# design_block_rev3_4.net
KiCad netlist of a schematic drawn in EAGLE
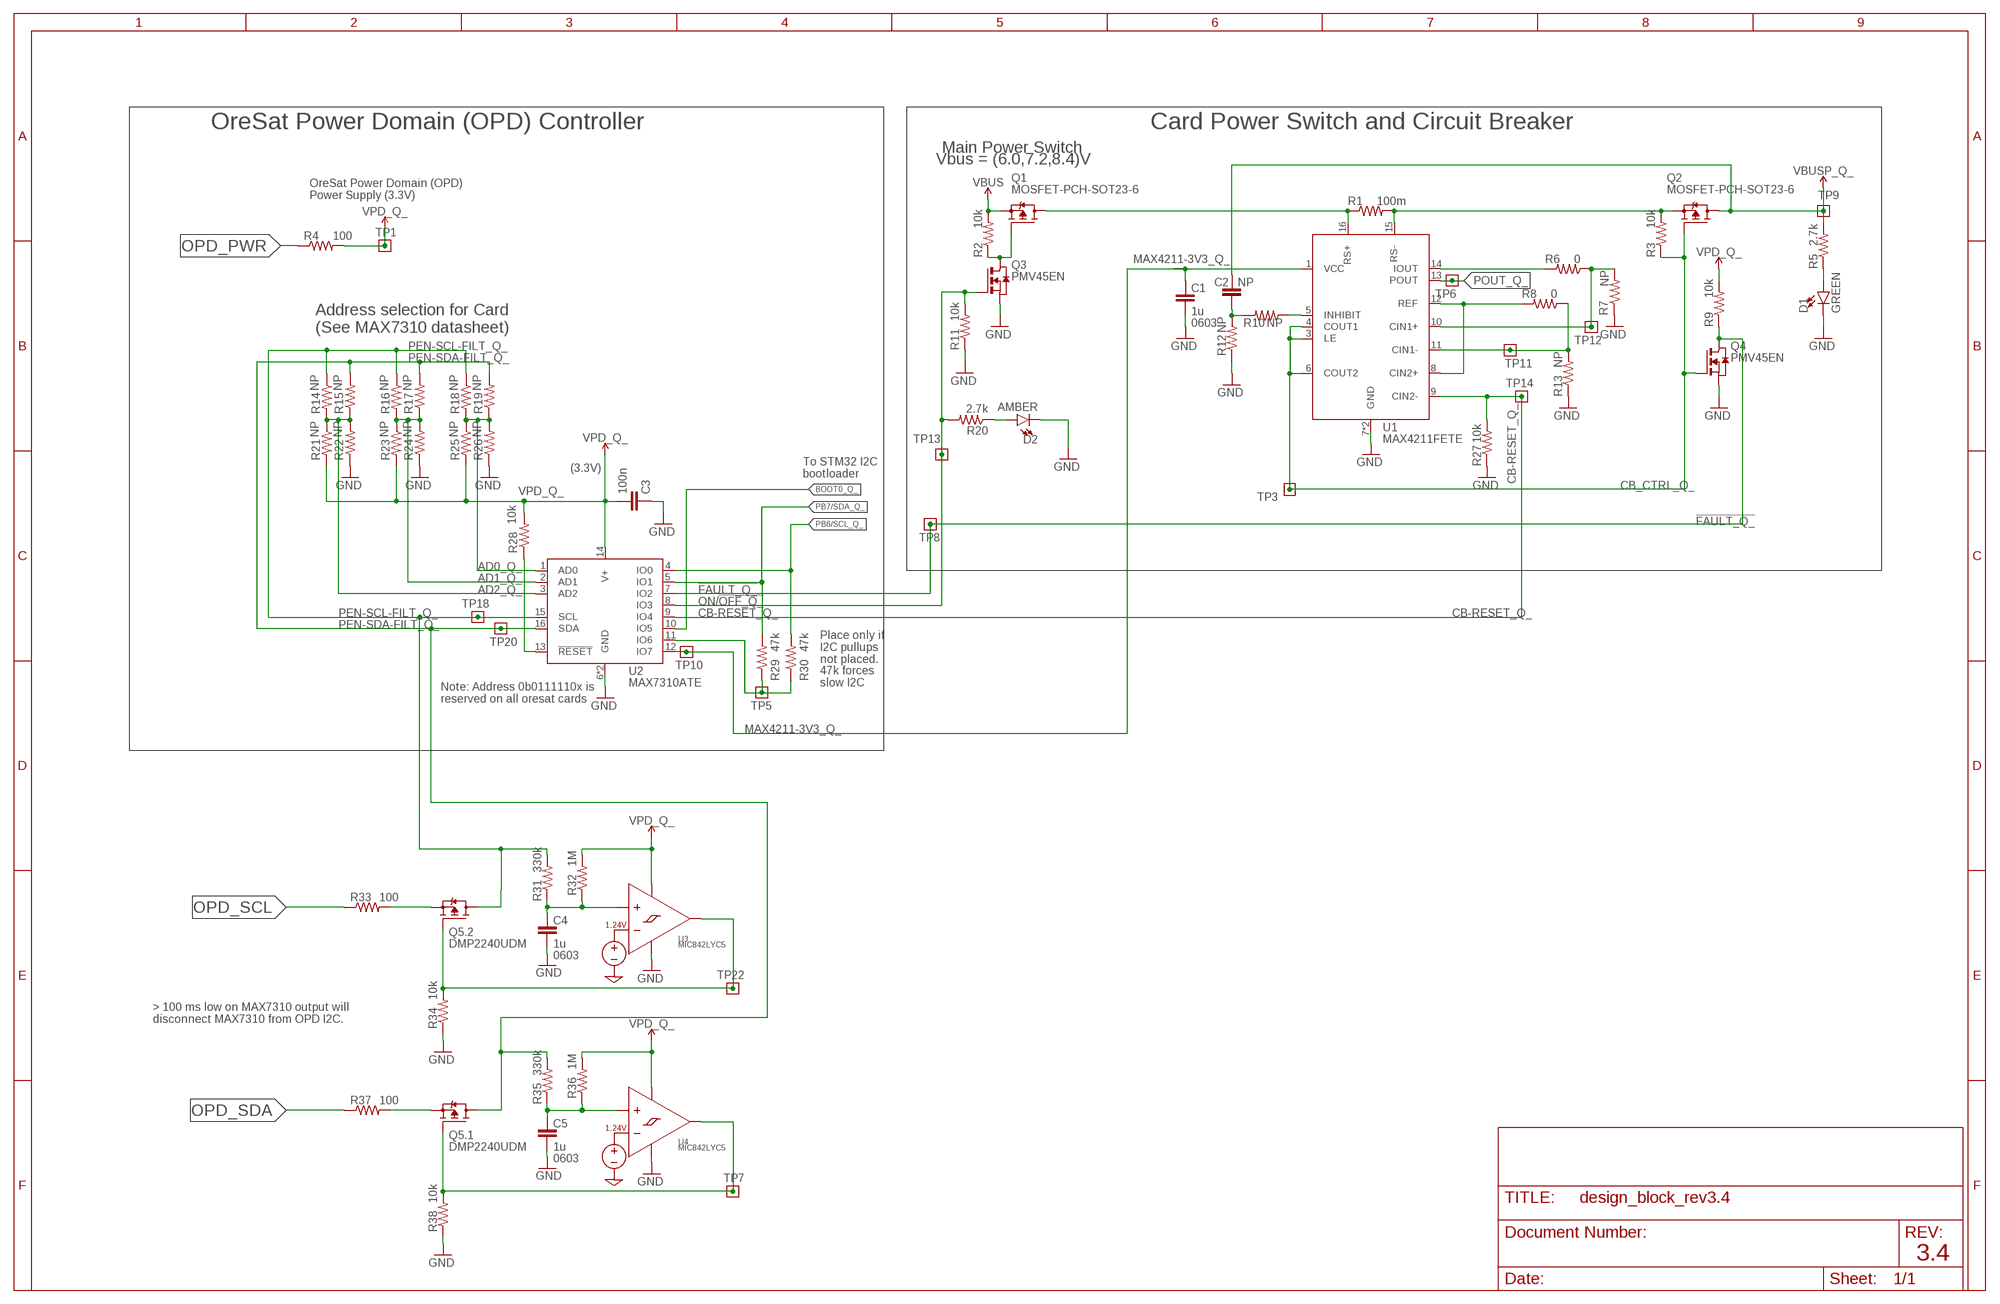
[diagram p0: schematic, sheet 1]

(export (version "E")
  (design (tool "Eeschema 10.0.6"))
  (components
    (comp (ref "C1")
      (value "1u")
      (footprint "eagle-import:.0603-B-NOSILK")
      (fields (field (name "MFR") "Yageo") (field (name "MPN") "CC0603KRX7R7BB105"))
      (libsource (lib "eagle-import") (part "C-EU0603-B-NOSILK"))
    )
    (comp (ref "C2")
      (value "NP")
      (footprint "eagle-import:.0402-B-NOSILK")
      (libsource (lib "eagle-import") (part "rcl_custom_C-EU0402-B-NOSILK"))
    )
    (comp (ref "C3")
      (value "100n")
      (footprint "eagle-import:.0402-B-NOSILK")
      (fields (field (name "MFR") "Samsung") (field (name "MPN") "CL05B104KO5NNNC"))
      (libsource (lib "eagle-import") (part "rcl_custom_C-EU0402-B-NOSILK"))
    )
    (comp (ref "C4")
      (value "1u")
      (footprint "eagle-import:.0603-B-NOSILK")
      (fields (field (name "MFR") "Yageo") (field (name "MPN") "CC0603KRX7R7BB105"))
      (libsource (lib "eagle-import") (part "C-EU0603-B-NOSILK"))
    )
    (comp (ref "C5")
      (value "1u")
      (footprint "eagle-import:.0603-B-NOSILK")
      (fields (field (name "MFR") "Yageo") (field (name "MPN") "CC0603KRX7R7BB105"))
      (libsource (lib "eagle-import") (part "C-EU0603-B-NOSILK"))
    )
    (comp (ref "D1")
      (value "GREEN")
      (footprint "eagle-import:LED-0603")
      (fields (field (name "MFR") "Rohm") (field (name "MPN") "SML-E12M8WT86"))
      (libsource (lib "eagle-import") (part "LED-GREEN0603"))
    )
    (comp (ref "D2")
      (value "AMBER")
      (footprint "eagle-import:LED-0603")
      (fields (field (name "MFR") "Inolux") (field (name "MPN") "IN-S63AT5A"))
      (libsource (lib "eagle-import") (part "LED-GREEN0603"))
    )
    (comp (ref "Q1")
      (value "MOSFET-PCH-SOT23-6")
      (footprint "eagle-import:SOT23-6")
      (fields (field (name "MFR") "Diodes Inc") (field (name "MPN") "DMP3050LVT-7"))
      (libsource (lib "eagle-import") (part "MOSFET-PCH-SOT23-6"))
    )
    (comp (ref "Q2")
      (value "MOSFET-PCH-SOT23-6")
      (footprint "eagle-import:SOT23-6")
      (fields (field (name "MFR") "Diodes Inc") (field (name "MPN") "DMP3050LVT-7"))
      (libsource (lib "eagle-import") (part "MOSFET-PCH-SOT23-6"))
    )
    (comp (ref "Q3")
      (value "PMV45EN")
      (footprint "eagle-import:SOT23")
      (fields (field (name "MFR") "Nexperia") (field (name "MPN") "PMV45EN2R"))
      (libsource (lib "eagle-import") (part "PMV45EN"))
    )
    (comp (ref "Q4")
      (value "PMV45EN")
      (footprint "eagle-import:SOT23")
      (fields (field (name "MFR") "Nexperia") (field (name "MPN") "PMV45EN2R"))
      (libsource (lib "eagle-import") (part "PMV45EN"))
    )
    (comp (ref "Q5")
      (value "DMP2240UDM")
      (footprint "eagle-import:SOT23-6")
      (fields
        (field (name "DIS") "Digi-Key")
        (field (name "DPN") "DMP2240UDMDICT-ND")
        (field (name "MFR") "Diodes Inc")
        (field (name "MPN") "DMP2240UDM")
      )
      (libsource (lib "eagle-import") (part "Q-MOSFET-PCH-dual-SOT23-6_MOSFET-PCH-SOT23-6"))
    )
    (comp (ref "R1")
      (value "100m")
      (footprint "eagle-import:R1206")
      (fields (field (name "MFR") "Stackpole") (field (name "MPN") "CSR1206FTR100"))
      (libsource (lib "eagle-import") (part "R-US_R1206"))
    )
    (comp (ref "R2")
      (value "10k")
      (footprint "eagle-import:.0402-B-NOSILK")
      (fields (field (name "MFR") "Yageo") (field (name "MPN") "RC0402FR-0710KL"))
      (libsource (lib "eagle-import") (part "R-US_0402-B-NOSILK"))
    )
    (comp (ref "R3")
      (value "10k")
      (footprint "eagle-import:.0402-B-NOSILK")
      (fields (field (name "MFR") "Yageo") (field (name "MPN") "RC0402FR-0710KL"))
      (libsource (lib "eagle-import") (part "R-US_0402-B-NOSILK"))
    )
    (comp (ref "R4")
      (value "100")
      (footprint "eagle-import:.0402-B-NOSILK")
      (fields (field (name "MFR") "Yageo") (field (name "MPN") "RC0402FR-07100RL"))
      (libsource (lib "eagle-import") (part "R-US_0402-B-NOSILK"))
    )
    (comp (ref "R5")
      (value "2.7k")
      (footprint "eagle-import:.0402-B-NOSILK")
      (fields (field (name "MFR") "TE Connectivity") (field (name "MPN") "CRGCQ0402F2K7"))
      (libsource (lib "eagle-import") (part "R-US_0402-B-NOSILK"))
    )
    (comp (ref "R6")
      (value "0")
      (footprint "eagle-import:.0402-B-NOSILK")
      (fields (field (name "MFR") "Yageo") (field (name "MPN") "RC0402JR-070RL"))
      (libsource (lib "eagle-import") (part "R-US_0402-B-NOSILK"))
    )
    (comp (ref "R7")
      (value "NP")
      (footprint "eagle-import:.0402-B-NOSILK")
      (fields (field (name "MFR") "Samsung") (field (name "MPN") "RC1005F6653CS"))
      (libsource (lib "eagle-import") (part "R-US_0402-B-NOSILK"))
    )
    (comp (ref "R8")
      (value "0")
      (footprint "eagle-import:.0402-B-NOSILK")
      (fields (field (name "MFR") "Yageo") (field (name "MPN") "RC0402JR-070RL"))
      (libsource (lib "eagle-import") (part "R-US_0402-B-NOSILK"))
    )
    (comp (ref "R9")
      (value "10k")
      (footprint "eagle-import:.0402-B-NOSILK")
      (fields (field (name "MFR") "Yageo") (field (name "MPN") "RC0402FR-0710KL"))
      (libsource (lib "eagle-import") (part "R-US_0402-B-NOSILK"))
    )
    (comp (ref "R10")
      (value "NP")
      (footprint "eagle-import:.0402-B-NOSILK")
      (fields (field (name "MFR") "Samsung") (field (name "MPN") "RC1005F6653CS"))
      (libsource (lib "eagle-import") (part "R-US_0402-B-NOSILK"))
    )
    (comp (ref "R11")
      (value "10k")
      (footprint "eagle-import:.0402-B-NOSILK")
      (fields (field (name "MFR") "Yageo") (field (name "MPN") "RC0402FR-0710KL"))
      (libsource (lib "eagle-import") (part "R-US_0402-B-NOSILK"))
    )
    (comp (ref "R12")
      (value "NP")
      (footprint "eagle-import:.0402-B-NOSILK")
      (fields (field (name "MFR") "Samsung") (field (name "MPN") "RC1005F6653CS"))
      (libsource (lib "eagle-import") (part "R-US_0402-B-NOSILK"))
    )
    (comp (ref "R13")
      (value "NP")
      (footprint "eagle-import:.0402-B-NOSILK")
      (fields (field (name "MFR") "Samsung") (field (name "MPN") "RC1005F6653CS"))
      (libsource (lib "eagle-import") (part "R-US_0402-B-NOSILK"))
    )
    (comp (ref "R14")
      (value "NP")
      (footprint "eagle-import:.0402-B-NOSILK")
      (fields (field (name "MFR") "Samsung") (field (name "MPN") "RC1005F6653CS"))
      (libsource (lib "eagle-import") (part "R-US_0402-B-NOSILK"))
    )
    (comp (ref "R15")
      (value "NP")
      (footprint "eagle-import:.0402-B-NOSILK")
      (fields (field (name "MFR") "Samsung") (field (name "MPN") "RC1005F6653CS"))
      (libsource (lib "eagle-import") (part "R-US_0402-B-NOSILK"))
    )
    (comp (ref "R16")
      (value "NP")
      (footprint "eagle-import:.0402-B-NOSILK")
      (fields (field (name "MFR") "Samsung") (field (name "MPN") "RC1005F6653CS"))
      (libsource (lib "eagle-import") (part "R-US_0402-B-NOSILK"))
    )
    (comp (ref "R17")
      (value "NP")
      (footprint "eagle-import:.0402-B-NOSILK")
      (fields (field (name "MFR") "Samsung") (field (name "MPN") "RC1005F6653CS"))
      (libsource (lib "eagle-import") (part "R-US_0402-B-NOSILK"))
    )
    (comp (ref "R18")
      (value "NP")
      (footprint "eagle-import:.0402-B-NOSILK")
      (fields (field (name "MFR") "Samsung") (field (name "MPN") "RC1005F6653CS"))
      (libsource (lib "eagle-import") (part "R-US_0402-B-NOSILK"))
    )
    (comp (ref "R19")
      (value "NP")
      (footprint "eagle-import:.0402-B-NOSILK")
      (fields (field (name "MFR") "Samsung") (field (name "MPN") "RC1005F6653CS"))
      (libsource (lib "eagle-import") (part "R-US_0402-B-NOSILK"))
    )
    (comp (ref "R20")
      (value "2.7k")
      (footprint "eagle-import:.0402-B-NOSILK")
      (fields (field (name "MFR") "TE Connectivity ") (field (name "MPN") "CRGCQ0402F2K7"))
      (libsource (lib "eagle-import") (part "R-US_0402-B-NOSILK"))
    )
    (comp (ref "R21")
      (value "NP")
      (footprint "eagle-import:.0402-B-NOSILK")
      (fields (field (name "MFR") "Samsung") (field (name "MPN") "RC1005F6653CS"))
      (libsource (lib "eagle-import") (part "R-US_0402-B-NOSILK"))
    )
    (comp (ref "R22")
      (value "NP")
      (footprint "eagle-import:.0402-B-NOSILK")
      (fields (field (name "MFR") "Samsung") (field (name "MPN") "RC1005F6653CS"))
      (libsource (lib "eagle-import") (part "R-US_0402-B-NOSILK"))
    )
    (comp (ref "R23")
      (value "NP")
      (footprint "eagle-import:.0402-B-NOSILK")
      (fields (field (name "MFR") "Samsung") (field (name "MPN") "RC1005F6653CS"))
      (libsource (lib "eagle-import") (part "R-US_0402-B-NOSILK"))
    )
    (comp (ref "R24")
      (value "NP")
      (footprint "eagle-import:.0402-B-NOSILK")
      (fields (field (name "MFR") "Samsung") (field (name "MPN") "RC1005F6653CS"))
      (libsource (lib "eagle-import") (part "R-US_0402-B-NOSILK"))
    )
    (comp (ref "R25")
      (value "NP")
      (footprint "eagle-import:.0402-B-NOSILK")
      (fields (field (name "MFR") "Samsung") (field (name "MPN") "RC1005F6653CS"))
      (libsource (lib "eagle-import") (part "R-US_0402-B-NOSILK"))
    )
    (comp (ref "R26")
      (value "NP")
      (footprint "eagle-import:.0402-B-NOSILK")
      (fields (field (name "MFR") "Samsung") (field (name "MPN") "RC1005F6653CS"))
      (libsource (lib "eagle-import") (part "R-US_0402-B-NOSILK"))
    )
    (comp (ref "R27")
      (value "10k")
      (footprint "eagle-import:.0402-B-NOSILK")
      (fields (field (name "MFR") "Yageo") (field (name "MPN") "RC0402FR-0710KL"))
      (libsource (lib "eagle-import") (part "R-US_0402-B-NOSILK"))
    )
    (comp (ref "R28")
      (value "10k")
      (footprint "eagle-import:.0402-B-NOSILK")
      (fields (field (name "MFR") "Yageo") (field (name "MPN") "RC0402FR-0710KL"))
      (libsource (lib "eagle-import") (part "R-US_0402-B-NOSILK"))
    )
    (comp (ref "R29")
      (value "47k")
      (footprint "eagle-import:.0402-B-NOSILK")
      (fields (field (name "MFR") "Yageo") (field (name "MPN") "RC0402FR-0747KL"))
      (libsource (lib "eagle-import") (part "R-US_0402-B-NOSILK"))
    )
    (comp (ref "R30")
      (value "47k")
      (footprint "eagle-import:.0402-B-NOSILK")
      (fields (field (name "MFR") "Yageo") (field (name "MPN") "RC0402FR-0747KL"))
      (libsource (lib "eagle-import") (part "R-US_0402-B-NOSILK"))
    )
    (comp (ref "R31")
      (value "330k")
      (footprint "eagle-import:.0402-B-NOSILK")
      (fields (field (name "MFR") "Vishay") (field (name "MPN") "MCS04020C3303FE000"))
      (libsource (lib "eagle-import") (part "R-US_0402-B-NOSILK"))
    )
    (comp (ref "R32")
      (value "1M")
      (footprint "eagle-import:.0402-B-NOSILK")
      (fields (field (name "MFR") "Yageo") (field (name "MPN") "RC0402FR-071ML"))
      (libsource (lib "eagle-import") (part "R-US_0402-B-NOSILK"))
    )
    (comp (ref "R33")
      (value "100")
      (footprint "eagle-import:.0402-B-NOSILK")
      (fields (field (name "MFR") "Yageo") (field (name "MPN") "RC0402FR-07100RL"))
      (libsource (lib "eagle-import") (part "R-US_0402-B-NOSILK"))
    )
    (comp (ref "R34")
      (value "10k")
      (footprint "eagle-import:.0402-B-NOSILK")
      (fields (field (name "MFR") "Yageo") (field (name "MPN") "RC0402FR-0710KL"))
      (libsource (lib "eagle-import") (part "R-US_0402-B-NOSILK"))
    )
    (comp (ref "R35")
      (value "330k")
      (footprint "eagle-import:.0402-B-NOSILK")
      (fields (field (name "MFR") "Vishay") (field (name "MPN") "MCS04020C3303FE000"))
      (libsource (lib "eagle-import") (part "R-US_0402-B-NOSILK"))
    )
    (comp (ref "R36")
      (value "1M")
      (footprint "eagle-import:.0402-B-NOSILK")
      (fields (field (name "MFR") "Yageo") (field (name "MPN") "RC0402FR-071ML"))
      (libsource (lib "eagle-import") (part "R-US_0402-B-NOSILK"))
    )
    (comp (ref "R37")
      (value "100")
      (footprint "eagle-import:.0402-B-NOSILK")
      (fields (field (name "MFR") "Yageo") (field (name "MPN") "RC0402FR-07100RL"))
      (libsource (lib "eagle-import") (part "R-US_0402-B-NOSILK"))
    )
    (comp (ref "R38")
      (value "10k")
      (footprint "eagle-import:.0402-B-NOSILK")
      (fields (field (name "MFR") "Yageo") (field (name "MPN") "RC0402FR-0710KL"))
      (libsource (lib "eagle-import") (part "R-US_0402-B-NOSILK"))
    )
    (comp (ref "TP1")
      (value "TEST-POINT")
      (footprint "eagle-import:2MM-TEST-POINT")
      (libsource (lib "eagle-import") (part "TEST-POINT"))
    )
    (comp (ref "TP3")
      (value "TEST-POINT")
      (footprint "eagle-import:2MM-TEST-POINT")
      (libsource (lib "eagle-import") (part "TEST-POINT"))
    )
    (comp (ref "TP5")
      (value "TEST-POINT")
      (footprint "eagle-import:2MM-TEST-POINT")
      (libsource (lib "eagle-import") (part "TEST-POINT"))
    )
    (comp (ref "TP6")
      (value "TEST-POINT")
      (footprint "eagle-import:2MM-TEST-POINT")
      (libsource (lib "eagle-import") (part "TEST-POINT"))
    )
    (comp (ref "TP7")
      (value "TEST-POINT")
      (footprint "eagle-import:2MM-TEST-POINT")
      (libsource (lib "eagle-import") (part "TEST-POINT"))
    )
    (comp (ref "TP8")
      (value "TEST-POINT")
      (footprint "eagle-import:2MM-TEST-POINT")
      (libsource (lib "eagle-import") (part "TEST-POINT"))
    )
    (comp (ref "TP9")
      (value "TEST-POINT")
      (footprint "eagle-import:2MM-TEST-POINT")
      (libsource (lib "eagle-import") (part "TEST-POINT"))
    )
    (comp (ref "TP10")
      (value "TEST-POINT")
      (footprint "eagle-import:2MM-TEST-POINT")
      (libsource (lib "eagle-import") (part "TEST-POINT"))
    )
    (comp (ref "TP11")
      (value "TEST-POINT")
      (footprint "eagle-import:2MM-TEST-POINT")
      (libsource (lib "eagle-import") (part "TEST-POINT"))
    )
    (comp (ref "TP12")
      (value "TEST-POINT")
      (footprint "eagle-import:2MM-TEST-POINT")
      (libsource (lib "eagle-import") (part "TEST-POINT"))
    )
    (comp (ref "TP13")
      (value "TEST-POINT")
      (footprint "eagle-import:2MM-TEST-POINT")
      (libsource (lib "eagle-import") (part "TEST-POINT"))
    )
    (comp (ref "TP14")
      (value "TEST-POINT")
      (footprint "eagle-import:2MM-TEST-POINT")
      (libsource (lib "eagle-import") (part "TEST-POINT"))
    )
    (comp (ref "TP18")
      (value "TEST-POINT")
      (footprint "eagle-import:2MM-TEST-POINT")
      (libsource (lib "eagle-import") (part "TEST-POINT"))
    )
    (comp (ref "TP20")
      (value "TEST-POINT")
      (footprint "eagle-import:2MM-TEST-POINT")
      (libsource (lib "eagle-import") (part "TEST-POINT"))
    )
    (comp (ref "TP22")
      (value "TEST-POINT")
      (footprint "eagle-import:2MM-TEST-POINT")
      (libsource (lib "eagle-import") (part "TEST-POINT"))
    )
    (comp (ref "U1")
      (value "MAX4211FETE")
      (footprint "eagle-import:QFN65P400X400X80-17T210")
      (fields (field (name "MFR") "Maxim"))
      (libsource (lib "eagle-import") (part "MAX4211"))
    )
    (comp (ref "U2")
      (value "MAX7310ATE")
      (footprint "eagle-import:QFN65P400X400X80-17T210")
      (fields (field (name "MFR") "Maxim"))
      (libsource (lib "eagle-import") (part "MAX7310"))
    )
    (comp (ref "U3")
      (value "MIC842LYC5")
      (footprint "eagle-import:SC70-5")
      (libsource (lib "eagle-import") (part "MIC842LYC5"))
    )
    (comp (ref "U4")
      (value "MIC842LYC5")
      (footprint "eagle-import:SC70-5")
      (libsource (lib "eagle-import") (part "MIC842LYC5"))
    )
  )
  (nets
    (net (code "1") (name "/AD0_Q_") (class "Default")
      (node (ref "R18") (pin "2") (pinfunction "2_2") (pintype "passive"))
      (node (ref "R19") (pin "1") (pinfunction "1_1") (pintype "passive"))
      (node (ref "R25") (pin "1") (pinfunction "1_1") (pintype "passive"))
      (node (ref "R26") (pin "2") (pinfunction "2_2") (pintype "passive"))
      (node (ref "U2") (pin "1") (pinfunction "AD0_1") (pintype "input"))
    )
    (net (code "2") (name "/AD1_Q_") (class "Default")
      (node (ref "R16") (pin "2") (pinfunction "2_2") (pintype "passive"))
      (node (ref "R17") (pin "1") (pinfunction "1_1") (pintype "passive"))
      (node (ref "R23") (pin "1") (pinfunction "1_1") (pintype "passive"))
      (node (ref "R24") (pin "2") (pinfunction "2_2") (pintype "passive"))
      (node (ref "U2") (pin "2") (pinfunction "AD1_2") (pintype "input"))
    )
    (net (code "3") (name "/AD2_Q_") (class "Default")
      (node (ref "R14") (pin "2") (pinfunction "2_2") (pintype "passive"))
      (node (ref "R15") (pin "1") (pinfunction "1_1") (pintype "passive"))
      (node (ref "R21") (pin "1") (pinfunction "1_1") (pintype "passive"))
      (node (ref "R22") (pin "2") (pinfunction "2_2") (pintype "passive"))
      (node (ref "U2") (pin "3") (pinfunction "AD2_3") (pintype "input"))
    )
    (net (code "4") (name "/CB-RESET_Q_") (class "Default")
      (node (ref "R27") (pin "2") (pinfunction "2_2") (pintype "passive"))
      (node (ref "TP14") (pin "1") (pinfunction "1_1") (pintype "passive"))
      (node (ref "U1") (pin "9") (pinfunction "CIN2-_9") (pintype "input"))
      (node (ref "U2") (pin "9") (pinfunction "IO4_9") (pintype "bidirectional"))
    )
    (net (code "5") (name "/CB_CTRL_Q_") (class "Default")
      (node (ref "Q2") (pin "3") (pinfunction "G_3") (pintype "passive"))
      (node (ref "Q4") (pin "1") (pinfunction "G_1") (pintype "passive"))
      (node (ref "R3") (pin "1") (pinfunction "1_1") (pintype "passive"))
      (node (ref "TP3") (pin "1") (pinfunction "1_1") (pintype "passive"))
      (node (ref "U1") (pin "3") (pinfunction "LE_3") (pintype "input"))
      (node (ref "U1") (pin "4") (pinfunction "COUT1_4") (pintype "open_collector"))
      (node (ref "U1") (pin "6") (pinfunction "COUT2_6") (pintype "open_collector"))
    )
    (net (code "6") (name "/MAX4211-3V3_Q_") (class "Default")
      (node (ref "C1") (pin "1") (pinfunction "1_1") (pintype "passive"))
      (node (ref "TP10") (pin "1") (pinfunction "1_1") (pintype "passive"))
      (node (ref "U1") (pin "1") (pinfunction "VCC_1") (pintype "power_in"))
      (node (ref "U2") (pin "12") (pinfunction "IO7_12") (pintype "bidirectional"))
    )
    (net (code "7") (name "/ON{slash}~{OFF_Q_}") (class "Default")
      (node (ref "Q3") (pin "1") (pinfunction "G_1") (pintype "passive"))
      (node (ref "R11") (pin "2") (pinfunction "2_2") (pintype "passive"))
      (node (ref "R20") (pin "2") (pinfunction "2_2") (pintype "passive"))
      (node (ref "TP13") (pin "1") (pinfunction "1_1") (pintype "passive"))
      (node (ref "U2") (pin "8") (pinfunction "IO3_8") (pintype "bidirectional"))
    )
    (net (code "8") (name "/PEN-SCL-FILT_Q_") (class "Default")
      (node (ref "Q5") (pin "4") (pinfunction "D_4") (pintype "passive"))
      (node (ref "R14") (pin "1") (pinfunction "1_1") (pintype "passive"))
      (node (ref "R16") (pin "1") (pinfunction "1_1") (pintype "passive"))
      (node (ref "R18") (pin "1") (pinfunction "1_1") (pintype "passive"))
      (node (ref "R31") (pin "2") (pinfunction "2_2") (pintype "passive"))
      (node (ref "TP18") (pin "1") (pinfunction "1_1") (pintype "passive"))
      (node (ref "U2") (pin "15") (pinfunction "SCL_15") (pintype "input"))
    )
    (net (code "9") (name "/PEN-SDA-FILT_Q_") (class "Default")
      (node (ref "Q5") (pin "6") (pinfunction "D_6") (pintype "passive"))
      (node (ref "R15") (pin "2") (pinfunction "2_2") (pintype "passive"))
      (node (ref "R17") (pin "2") (pinfunction "2_2") (pintype "passive"))
      (node (ref "R19") (pin "2") (pinfunction "2_2") (pintype "passive"))
      (node (ref "R35") (pin "2") (pinfunction "2_2") (pintype "passive"))
      (node (ref "TP20") (pin "1") (pinfunction "1_1") (pintype "passive"))
      (node (ref "U2") (pin "16") (pinfunction "SDA_16") (pintype "bidirectional"))
    )
    (net (code "10") (name "/~{FAULT_Q_}") (class "Default")
      (node (ref "Q4") (pin "3") (pinfunction "D_3") (pintype "passive"))
      (node (ref "R9") (pin "1") (pinfunction "1_1") (pintype "passive"))
      (node (ref "TP8") (pin "1") (pinfunction "1_1") (pintype "passive"))
      (node (ref "U2") (pin "7") (pinfunction "IO2_7") (pintype "bidirectional"))
    )
    (net (code "11") (name "BOOT0_Q_") (class "Default")
      (node (ref "U2") (pin "10") (pinfunction "IO5_10") (pintype "bidirectional"))
    )
    (net (code "12") (name "GND") (class "Default")
      (node (ref "C1") (pin "2") (pinfunction "2_2") (pintype "passive"))
      (node (ref "C3") (pin "1") (pinfunction "1_1") (pintype "passive"))
      (node (ref "C4") (pin "2") (pinfunction "2_2") (pintype "passive"))
      (node (ref "C5") (pin "2") (pinfunction "2_2") (pintype "passive"))
      (node (ref "D1") (pin "C") (pinfunction "C_C") (pintype "passive"))
      (node (ref "D2") (pin "C") (pinfunction "C_C") (pintype "passive"))
      (node (ref "Q3") (pin "2") (pinfunction "S_2") (pintype "passive"))
      (node (ref "Q4") (pin "2") (pinfunction "S_2") (pintype "passive"))
      (node (ref "R11") (pin "1") (pinfunction "1_1") (pintype "passive"))
      (node (ref "R12") (pin "1") (pinfunction "1_1") (pintype "passive"))
      (node (ref "R13") (pin "1") (pinfunction "1_1") (pintype "passive"))
      (node (ref "R22") (pin "1") (pinfunction "1_1") (pintype "passive"))
      (node (ref "R24") (pin "1") (pinfunction "1_1") (pintype "passive"))
      (node (ref "R26") (pin "1") (pinfunction "1_1") (pintype "passive"))
      (node (ref "R27") (pin "1") (pinfunction "1_1") (pintype "passive"))
      (node (ref "R34") (pin "1") (pinfunction "1_1") (pintype "passive"))
      (node (ref "R38") (pin "1") (pinfunction "1_1") (pintype "passive"))
      (node (ref "R7") (pin "1") (pinfunction "1_1") (pintype "passive"))
      (node (ref "U1") (pin "7") (pinfunction "GND_7") (pintype "power_in"))
      (node (ref "U1") (pin "EPAD") (pinfunction "GND_EPAD") (pintype "power_in"))
      (node (ref "U2") (pin "6") (pinfunction "GND_6") (pintype "power_in"))
      (node (ref "U2") (pin "EPAD") (pinfunction "GND_EPAD") (pintype "power_in"))
      (node (ref "U3") (pin "2") (pinfunction "GND_2") (pintype "power_in"))
      (node (ref "U4") (pin "2") (pinfunction "GND_2") (pintype "power_in"))
    )
    (net (code "13") (name "Net-(C2-Pad1)") (class "Default")
      (node (ref "C2") (pin "1") (pinfunction "1_1") (pintype "passive"))
      (node (ref "R10") (pin "2") (pinfunction "2_2") (pintype "passive"))
      (node (ref "R12") (pin "2") (pinfunction "2_2") (pintype "passive"))
    )
    (net (code "14") (name "Net-(D1-PadA)") (class "Default")
      (node (ref "D1") (pin "A") (pinfunction "A_A") (pintype "passive"))
      (node (ref "R5") (pin "1") (pinfunction "1_1") (pintype "passive"))
    )
    (net (code "15") (name "Net-(D2-PadA)") (class "Default")
      (node (ref "D2") (pin "A") (pinfunction "A_A") (pintype "passive"))
      (node (ref "R20") (pin "1") (pinfunction "1_1") (pintype "passive"))
    )
    (net (code "16") (name "Net-(Q1-G)") (class "Default")
      (node (ref "Q1") (pin "3") (pinfunction "G_3") (pintype "passive"))
      (node (ref "Q3") (pin "3") (pinfunction "D_3") (pintype "passive"))
      (node (ref "R2") (pin "1") (pinfunction "1_1") (pintype "passive"))
    )
    (net (code "17") (name "Net-(Q2-S)") (class "Default")
      (node (ref "Q2") (pin "4") (pinfunction "S_4") (pintype "passive"))
      (node (ref "R1") (pin "2") (pinfunction "2_2") (pintype "passive"))
      (node (ref "R3") (pin "2") (pinfunction "2_2") (pintype "passive"))
      (node (ref "U1") (pin "15") (pinfunction "RS-_15") (pintype "passive"))
    )
    (net (code "18") (name "Net-(Q5A-G)") (class "Default")
      (node (ref "Q5") (pin "1") (pinfunction "G_1") (pintype "passive"))
      (node (ref "R38") (pin "2") (pinfunction "2_2") (pintype "passive"))
      (node (ref "TP7") (pin "1") (pinfunction "1_1") (pintype "passive"))
      (node (ref "U4") (pin "4") (pinfunction "OUT_4") (pintype "output"))
    )
    (net (code "19") (name "Net-(Q5A-S)") (class "Default")
      (node (ref "Q5") (pin "5") (pinfunction "S_5") (pintype "passive"))
      (node (ref "R37") (pin "2") (pinfunction "2_2") (pintype "passive"))
    )
    (net (code "20") (name "Net-(Q5B-G)") (class "Default")
      (node (ref "Q5") (pin "3") (pinfunction "G_3") (pintype "passive"))
      (node (ref "R34") (pin "2") (pinfunction "2_2") (pintype "passive"))
      (node (ref "TP22") (pin "1") (pinfunction "1_1") (pintype "passive"))
      (node (ref "U3") (pin "4") (pinfunction "OUT_4") (pintype "output"))
    )
    (net (code "21") (name "Net-(Q5B-S)") (class "Default")
      (node (ref "Q5") (pin "2") (pinfunction "S_2") (pintype "passive"))
      (node (ref "R33") (pin "2") (pinfunction "2_2") (pintype "passive"))
    )
    (net (code "22") (name "Net-(U1-CIN1+)") (class "Default")
      (node (ref "R6") (pin "1") (pinfunction "1_1") (pintype "passive"))
      (node (ref "R7") (pin "2") (pinfunction "2_2") (pintype "passive"))
      (node (ref "TP12") (pin "1") (pinfunction "1_1") (pintype "passive"))
      (node (ref "U1") (pin "10") (pinfunction "CIN1+_10") (pintype "input"))
    )
    (net (code "23") (name "Net-(U1-CIN1-)") (class "Default")
      (node (ref "R13") (pin "2") (pinfunction "2_2") (pintype "passive"))
      (node (ref "R8") (pin "1") (pinfunction "1_1") (pintype "passive"))
      (node (ref "TP11") (pin "1") (pinfunction "1_1") (pintype "passive"))
      (node (ref "U1") (pin "11") (pinfunction "CIN1-_11") (pintype "input"))
    )
    (net (code "24") (name "Net-(U1-CIN2+)") (class "Default")
      (node (ref "R8") (pin "2") (pinfunction "2_2") (pintype "passive"))
      (node (ref "U1") (pin "12") (pinfunction "REF_12") (pintype "output"))
      (node (ref "U1") (pin "8") (pinfunction "CIN2+_8") (pintype "input"))
    )
    (net (code "25") (name "Net-(U1-INHIBIT)") (class "Default")
      (node (ref "R10") (pin "1") (pinfunction "1_1") (pintype "passive"))
      (node (ref "U1") (pin "5") (pinfunction "INHIBIT_5") (pintype "input"))
    )
    (net (code "26") (name "Net-(U1-IOUT)") (class "Default")
      (node (ref "R6") (pin "2") (pinfunction "2_2") (pintype "passive"))
      (node (ref "U1") (pin "14") (pinfunction "IOUT_14") (pintype "output"))
    )
    (net (code "27") (name "Net-(U1-RS+)") (class "Default")
      (node (ref "Q1") (pin "1") (pinfunction "D_1") (pintype "passive"))
      (node (ref "Q1") (pin "2") (pinfunction "D_2") (pintype "passive"))
      (node (ref "Q1") (pin "5") (pinfunction "D_5") (pintype "passive"))
      (node (ref "Q1") (pin "6") (pinfunction "D_6") (pintype "passive"))
      (node (ref "R1") (pin "1") (pinfunction "1_1") (pintype "passive"))
      (node (ref "U1") (pin "16") (pinfunction "RS+_16") (pintype "passive"))
    )
    (net (code "28") (name "Net-(U2-IO6)") (class "Default")
      (node (ref "R29") (pin "1") (pinfunction "1_1") (pintype "passive"))
      (node (ref "R30") (pin "1") (pinfunction "1_1") (pintype "passive"))
      (node (ref "TP5") (pin "1") (pinfunction "1_1") (pintype "passive"))
      (node (ref "U2") (pin "11") (pinfunction "IO6_11") (pintype "bidirectional"))
    )
    (net (code "29") (name "Net-(U2-~{RESET})") (class "Default")
      (node (ref "R28") (pin "1") (pinfunction "1_1") (pintype "passive"))
      (node (ref "U2") (pin "13") (pinfunction "~{RESET}_13") (pintype "input"))
    )
    (net (code "30") (name "Net-(U3-INP)") (class "Default")
      (node (ref "C4") (pin "1") (pinfunction "1_1") (pintype "passive"))
      (node (ref "R31") (pin "1") (pinfunction "1_1") (pintype "passive"))
      (node (ref "R32") (pin "1") (pinfunction "1_1") (pintype "passive"))
      (node (ref "U3") (pin "1") (pinfunction "INP_1") (pintype "input"))
    )
    (net (code "31") (name "Net-(U4-INP)") (class "Default")
      (node (ref "C5") (pin "1") (pinfunction "1_1") (pintype "passive"))
      (node (ref "R35") (pin "1") (pinfunction "1_1") (pintype "passive"))
      (node (ref "R36") (pin "1") (pinfunction "1_1") (pintype "passive"))
      (node (ref "U4") (pin "1") (pinfunction "INP_1") (pintype "input"))
    )
    (net (code "32") (name "OPD_PWR") (class "Default")
      (node (ref "R4") (pin "1") (pinfunction "1_1") (pintype "passive"))
    )
    (net (code "33") (name "OPD_SCL") (class "Default")
      (node (ref "R33") (pin "1") (pinfunction "1_1") (pintype "passive"))
    )
    (net (code "34") (name "OPD_SDA") (class "Default")
      (node (ref "R37") (pin "1") (pinfunction "1_1") (pintype "passive"))
    )
    (net (code "35") (name "PB6{slash}SCL_Q_") (class "Default")
      (node (ref "R30") (pin "2") (pinfunction "2_2") (pintype "passive"))
      (node (ref "U2") (pin "4") (pinfunction "IO0_4") (pintype "bidirectional"))
    )
    (net (code "36") (name "PB7{slash}SDA_Q_") (class "Default")
      (node (ref "R29") (pin "2") (pinfunction "2_2") (pintype "passive"))
      (node (ref "U2") (pin "5") (pinfunction "IO1_5") (pintype "bidirectional"))
    )
    (net (code "37") (name "POUT_Q_") (class "Default")
      (node (ref "TP6") (pin "1") (pinfunction "1_1") (pintype "passive"))
      (node (ref "U1") (pin "13") (pinfunction "POUT_13") (pintype "output"))
    )
    (net (code "38") (name "VBUS") (class "Default")
      (node (ref "Q1") (pin "4") (pinfunction "S_4") (pintype "passive"))
      (node (ref "R2") (pin "2") (pinfunction "2_2") (pintype "passive"))
    )
    (net (code "39") (name "VBUSP_Q_") (class "Default")
      (node (ref "C2") (pin "2") (pinfunction "2_2") (pintype "passive"))
      (node (ref "Q2") (pin "1") (pinfunction "D_1") (pintype "passive"))
      (node (ref "Q2") (pin "2") (pinfunction "D_2") (pintype "passive"))
      (node (ref "Q2") (pin "5") (pinfunction "D_5") (pintype "passive"))
      (node (ref "Q2") (pin "6") (pinfunction "D_6") (pintype "passive"))
      (node (ref "R5") (pin "2") (pinfunction "2_2") (pintype "passive"))
      (node (ref "TP9") (pin "1") (pinfunction "1_1") (pintype "passive"))
    )
    (net (code "40") (name "VPD_Q_") (class "Default")
      (node (ref "C3") (pin "2") (pinfunction "2_2") (pintype "passive"))
      (node (ref "R21") (pin "2") (pinfunction "2_2") (pintype "passive"))
      (node (ref "R23") (pin "2") (pinfunction "2_2") (pintype "passive"))
      (node (ref "R25") (pin "2") (pinfunction "2_2") (pintype "passive"))
      (node (ref "R28") (pin "2") (pinfunction "2_2") (pintype "passive"))
      (node (ref "R32") (pin "2") (pinfunction "2_2") (pintype "passive"))
      (node (ref "R36") (pin "2") (pinfunction "2_2") (pintype "passive"))
      (node (ref "R4") (pin "2") (pinfunction "2_2") (pintype "passive"))
      (node (ref "R9") (pin "2") (pinfunction "2_2") (pintype "passive"))
      (node (ref "TP1") (pin "1") (pinfunction "1_1") (pintype "passive"))
      (node (ref "U2") (pin "14") (pinfunction "V+_14") (pintype "power_in"))
      (node (ref "U3") (pin "5") (pinfunction "VDD_5") (pintype "power_in"))
      (node (ref "U4") (pin "5") (pinfunction "VDD_5") (pintype "power_in"))
    )
  )
)
